# MCU.net
KiCad netlist of a schematic drawn in Altium Designer
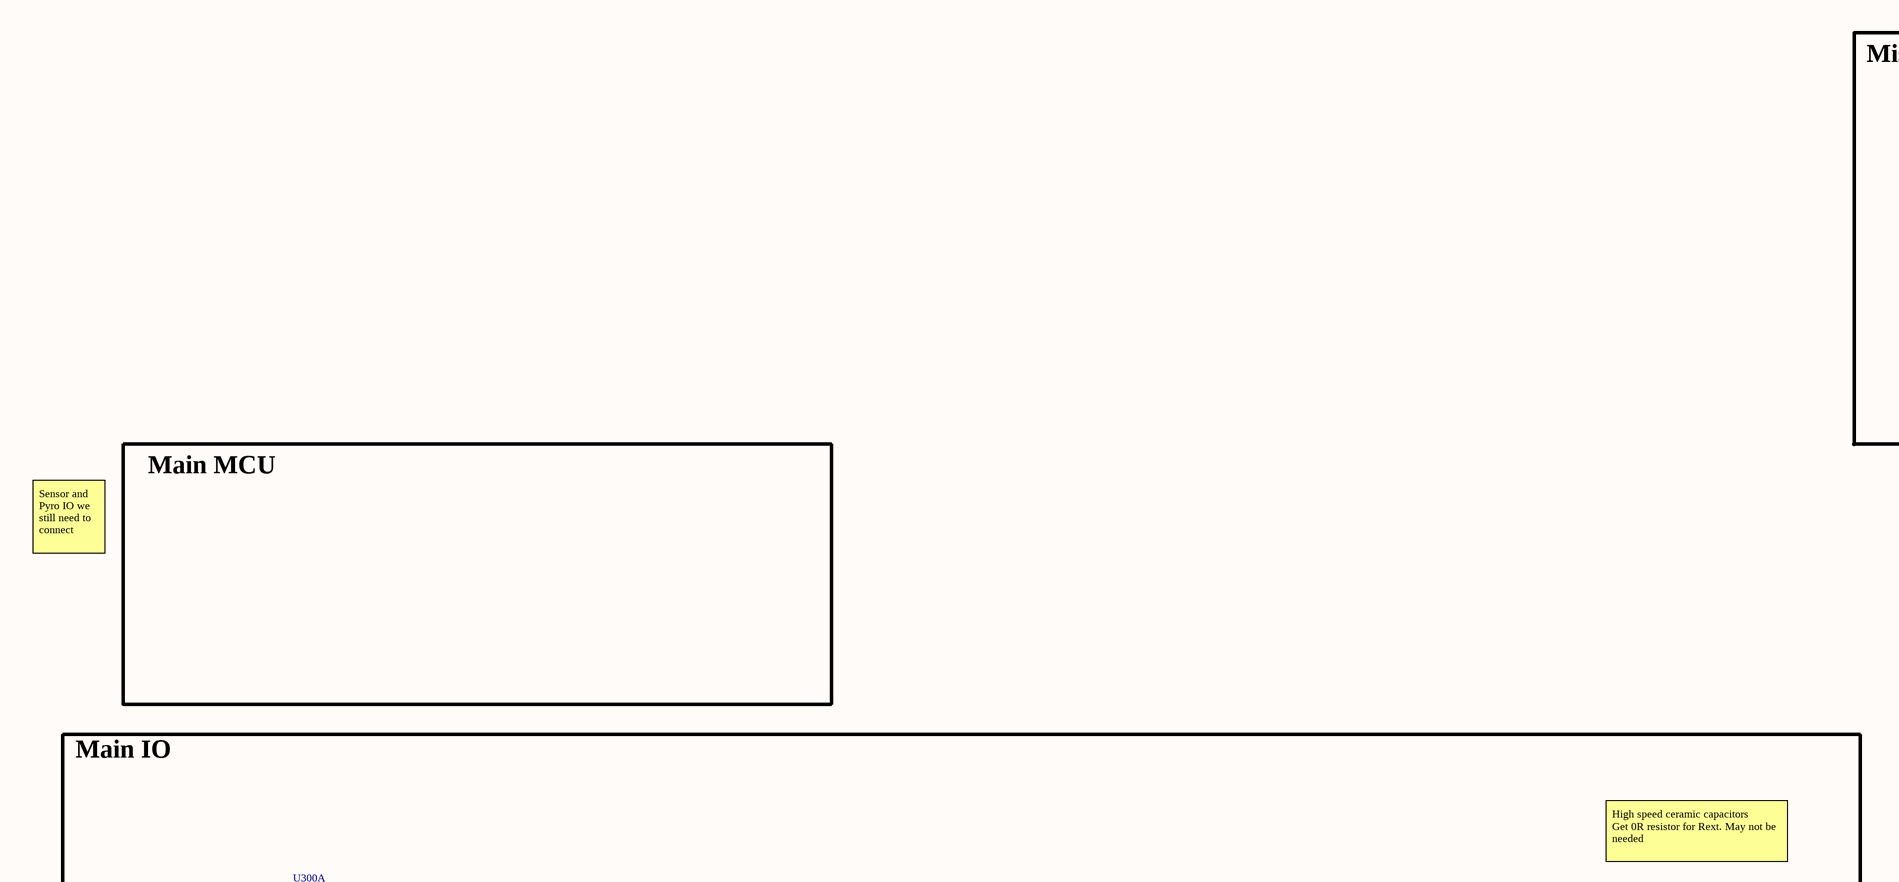
[diagram p0: MCU.SchDoc, top left]
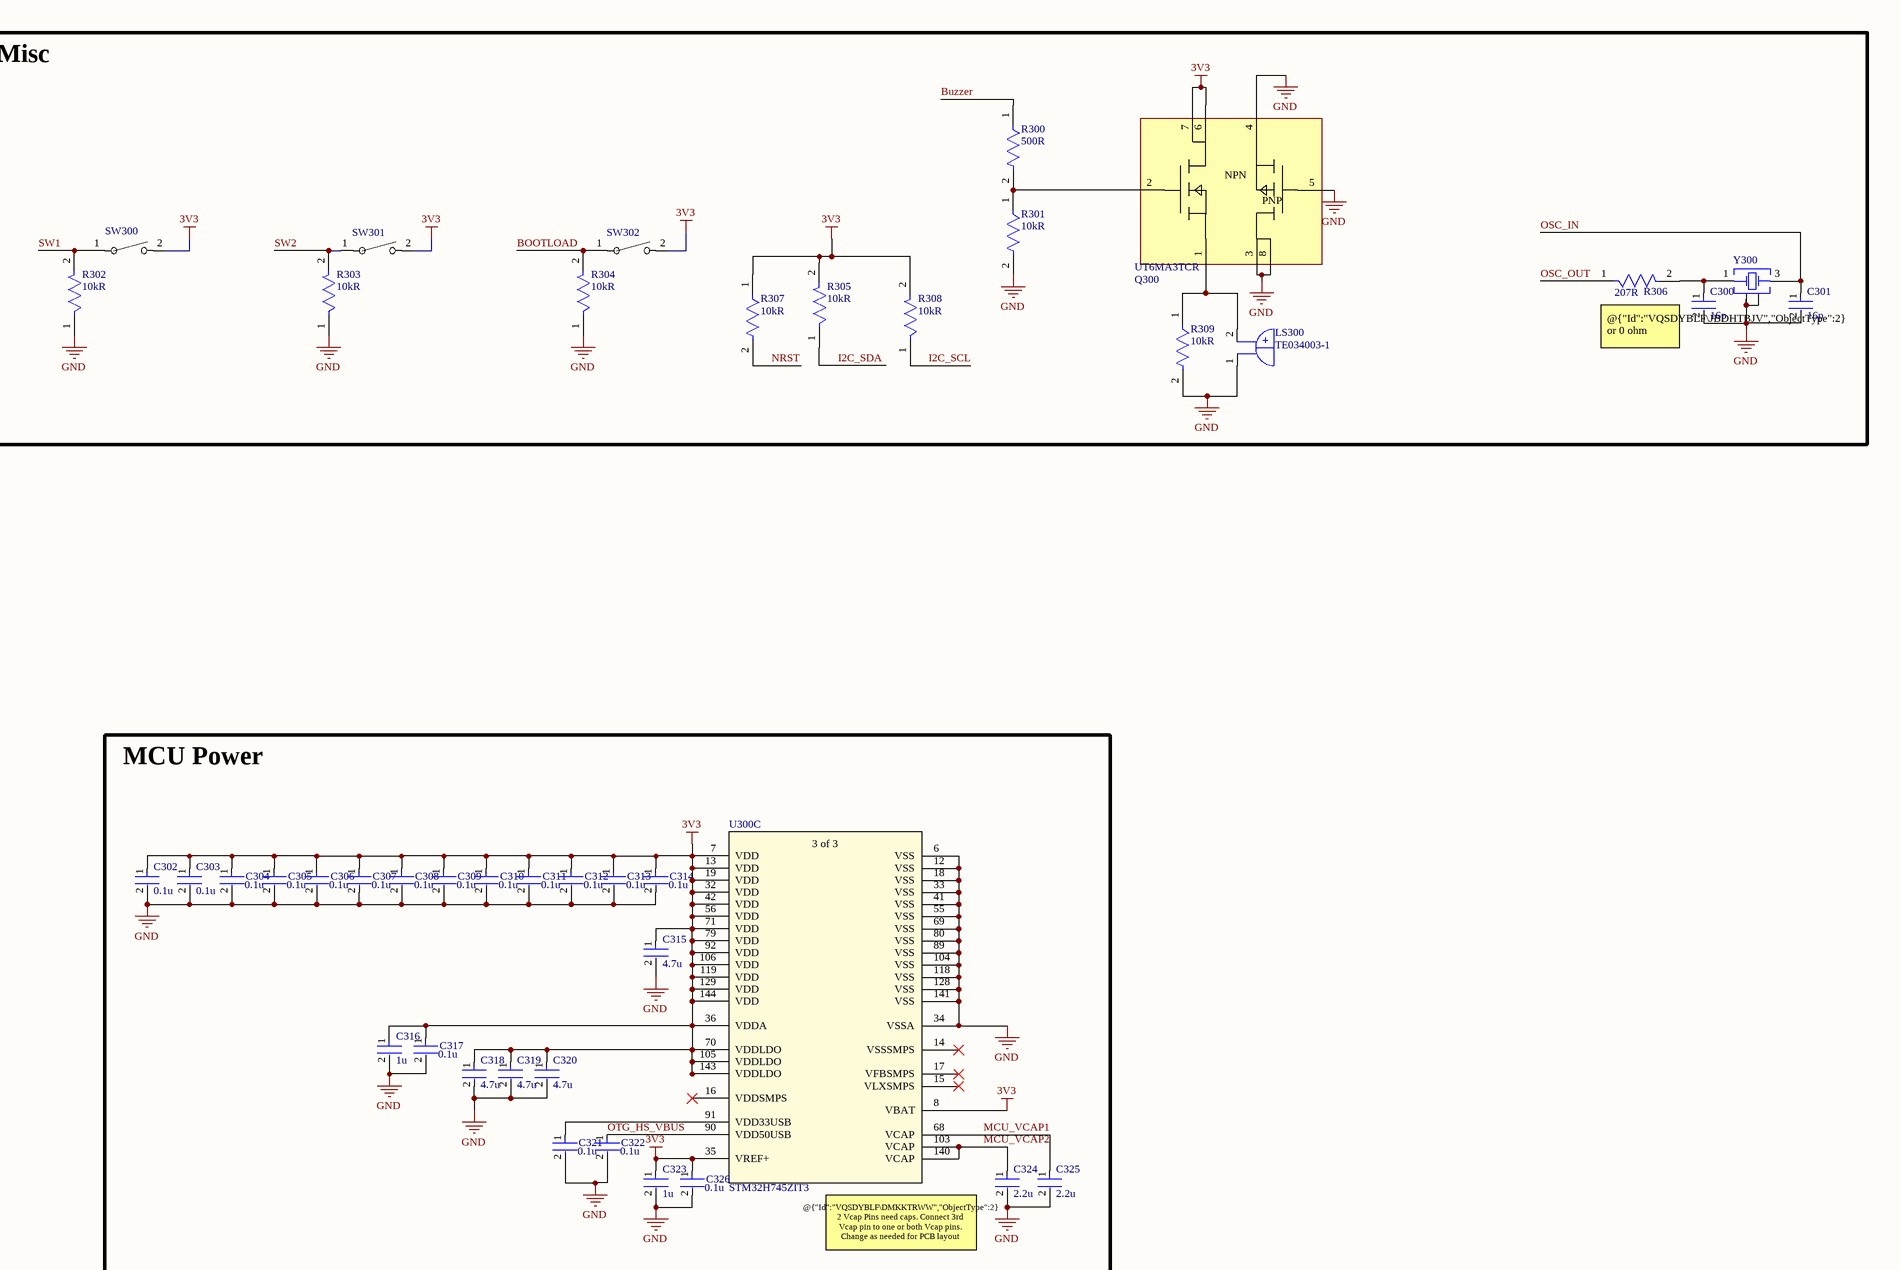
[diagram p1: MCU.SchDoc, top right]
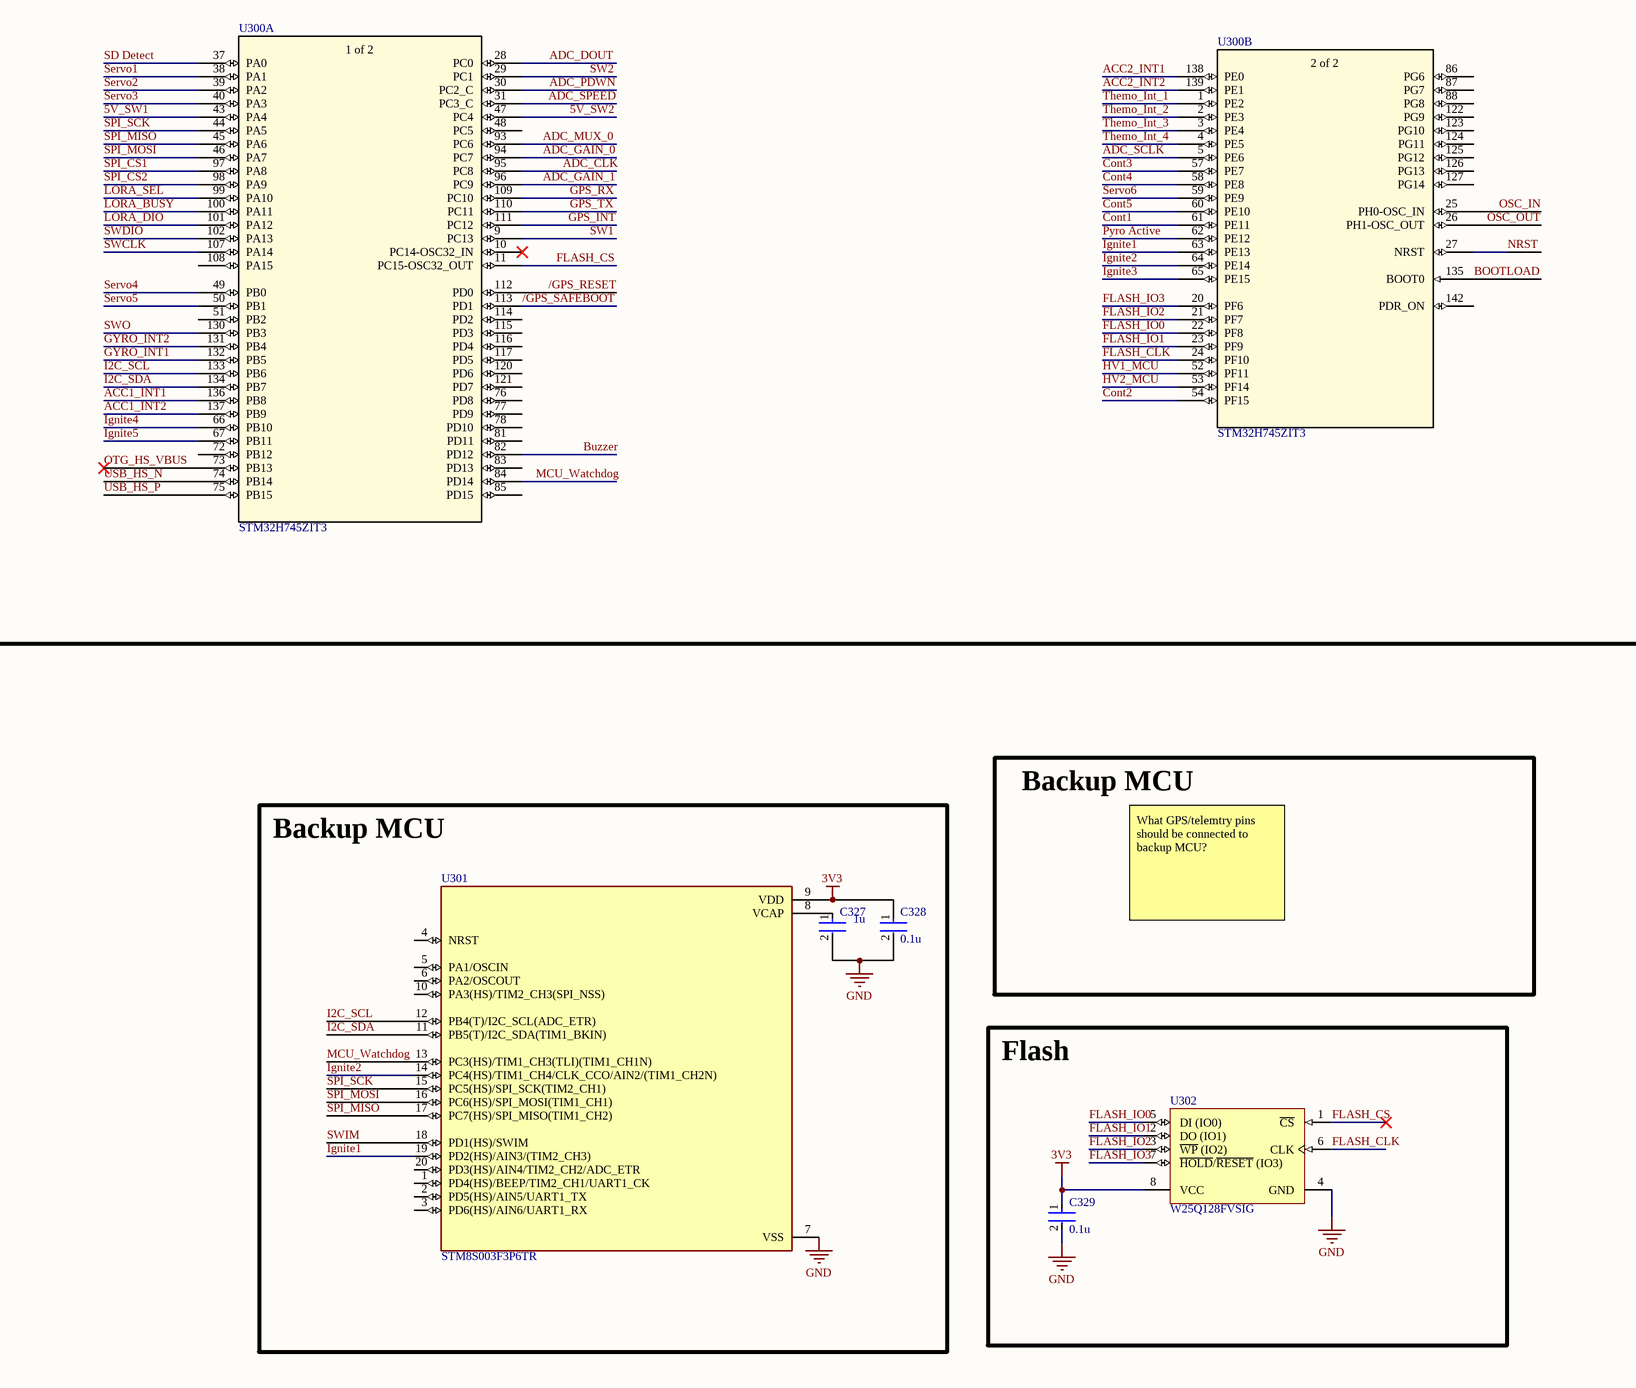
[diagram p2: MCU.SchDoc, bottom left]

(export (version "E")
  (design (tool "Eeschema 10.0.6"))
  (components
    (comp (ref "C300")
      (value "CL10C681JB8NFNC")
      (footprint "FP-CL10-IPC_A")
      (description "Cap Ceramic 680pF 50V C0G ±5% Pad SMD 0603 +125°C T/R")
      (fields (field (name "CAPACITANCE") "16p") (field (name "TOLERANCE") "5%"))
      (libsource (lib "Altium Content Vault") (part "b4654b650e69147ec39a6b967a45e02"))
    )
    (comp (ref "C301")
      (value "CL10C681JB8NFNC")
      (footprint "FP-CL10-IPC_A")
      (description "Cap Ceramic 680pF 50V C0G ±5% Pad SMD 0603 +125°C T/R")
      (fields (field (name "CAPACITANCE") "16p") (field (name "TOLERANCE") "5%"))
      (libsource (lib "Altium Content Vault") (part "b4654b650e69147ec39a6b967a45e02"))
    )
    (comp (ref "C302")
      (value "CL05B104KQ5NNNC")
      (footprint "FP-CL94-IPC_C")
      (description "Cap Ceramic 100nF 6.3V X7R ±10% SMD 0402 +125°C Paper T/R")
      (fields (field (name "TOLERANCE") "10%") (field (name "CAPACITANCE") "0.1u"))
      (libsource (lib "Altium Content Vault") (part "b4654b650e69147ec39a6b967a45e02"))
    )
    (comp (ref "C303")
      (value "CL05B104KQ5NNNC")
      (footprint "FP-CL94-IPC_C")
      (description "Cap Ceramic 100nF 6.3V X7R ±10% SMD 0402 +125°C Paper T/R")
      (fields (field (name "TOLERANCE") "10%") (field (name "CAPACITANCE") "0.1u"))
      (libsource (lib "Altium Content Vault") (part "b4654b650e69147ec39a6b967a45e02"))
    )
    (comp (ref "C304")
      (value "CL05B104KQ5NNNC")
      (footprint "FP-CL94-IPC_C")
      (description "Cap Ceramic 100nF 6.3V X7R ±10% SMD 0402 +125°C Paper T/R")
      (fields (field (name "TOLERANCE") "10%") (field (name "CAPACITANCE") "0.1u"))
      (libsource (lib "Altium Content Vault") (part "b4654b650e69147ec39a6b967a45e02"))
    )
    (comp (ref "C305")
      (value "CL05B104KQ5NNNC")
      (footprint "FP-CL94-IPC_C")
      (description "Cap Ceramic 100nF 6.3V X7R ±10% SMD 0402 +125°C Paper T/R")
      (fields (field (name "TOLERANCE") "10%") (field (name "CAPACITANCE") "0.1u"))
      (libsource (lib "Altium Content Vault") (part "b4654b650e69147ec39a6b967a45e02"))
    )
    (comp (ref "C306")
      (value "CL05B104KQ5NNNC")
      (footprint "FP-CL94-IPC_C")
      (description "Cap Ceramic 100nF 6.3V X7R ±10% SMD 0402 +125°C Paper T/R")
      (fields (field (name "TOLERANCE") "10%") (field (name "CAPACITANCE") "0.1u"))
      (libsource (lib "Altium Content Vault") (part "b4654b650e69147ec39a6b967a45e02"))
    )
    (comp (ref "C307")
      (value "CL05B104KQ5NNNC")
      (footprint "FP-CL94-IPC_C")
      (description "Cap Ceramic 100nF 6.3V X7R ±10% SMD 0402 +125°C Paper T/R")
      (fields (field (name "TOLERANCE") "10%") (field (name "CAPACITANCE") "0.1u"))
      (libsource (lib "Altium Content Vault") (part "b4654b650e69147ec39a6b967a45e02"))
    )
    (comp (ref "C308")
      (value "CL05B104KQ5NNNC")
      (footprint "FP-CL94-IPC_C")
      (description "Cap Ceramic 100nF 6.3V X7R ±10% SMD 0402 +125°C Paper T/R")
      (fields (field (name "TOLERANCE") "10%") (field (name "CAPACITANCE") "0.1u"))
      (libsource (lib "Altium Content Vault") (part "b4654b650e69147ec39a6b967a45e02"))
    )
    (comp (ref "C309")
      (value "CL05B104KQ5NNNC")
      (footprint "FP-CL94-IPC_C")
      (description "Cap Ceramic 100nF 6.3V X7R ±10% SMD 0402 +125°C Paper T/R")
      (fields (field (name "TOLERANCE") "10%") (field (name "CAPACITANCE") "0.1u"))
      (libsource (lib "Altium Content Vault") (part "b4654b650e69147ec39a6b967a45e02"))
    )
    (comp (ref "C310")
      (value "CL05B104KQ5NNNC")
      (footprint "FP-CL94-IPC_C")
      (description "Cap Ceramic 100nF 6.3V X7R ±10% SMD 0402 +125°C Paper T/R")
      (fields (field (name "TOLERANCE") "10%") (field (name "CAPACITANCE") "0.1u"))
      (libsource (lib "Altium Content Vault") (part "b4654b650e69147ec39a6b967a45e02"))
    )
    (comp (ref "C311")
      (value "CL05B104KQ5NNNC")
      (footprint "FP-CL94-IPC_C")
      (description "Cap Ceramic 100nF 6.3V X7R ±10% SMD 0402 +125°C Paper T/R")
      (fields (field (name "TOLERANCE") "10%") (field (name "CAPACITANCE") "0.1u"))
      (libsource (lib "Altium Content Vault") (part "b4654b650e69147ec39a6b967a45e02"))
    )
    (comp (ref "C312")
      (value "CL05B104KQ5NNNC")
      (footprint "FP-CL94-IPC_C")
      (description "Cap Ceramic 100nF 6.3V X7R ±10% SMD 0402 +125°C Paper T/R")
      (fields (field (name "TOLERANCE") "10%") (field (name "CAPACITANCE") "0.1u"))
      (libsource (lib "Altium Content Vault") (part "b4654b650e69147ec39a6b967a45e02"))
    )
    (comp (ref "C313")
      (value "CL05B104KQ5NNNC")
      (footprint "FP-CL94-IPC_C")
      (description "Cap Ceramic 100nF 6.3V X7R ±10% SMD 0402 +125°C Paper T/R")
      (fields (field (name "TOLERANCE") "10%") (field (name "CAPACITANCE") "0.1u"))
      (libsource (lib "Altium Content Vault") (part "b4654b650e69147ec39a6b967a45e02"))
    )
    (comp (ref "C314")
      (value "CL05B104KQ5NNNC")
      (footprint "FP-CL94-IPC_C")
      (description "Cap Ceramic 100nF 6.3V X7R ±10% SMD 0402 +125°C Paper T/R")
      (fields (field (name "TOLERANCE") "10%") (field (name "CAPACITANCE") "0.1u"))
      (libsource (lib "Altium Content Vault") (part "b4654b650e69147ec39a6b967a45e02"))
    )
    (comp (ref "C315")
      (value "CL10C681JB8NFNC")
      (footprint "FP-CL10-IPC_A")
      (description "Cap Ceramic 680pF 50V C0G ±5% Pad SMD 0603 +125°C T/R")
      (fields (field (name "CAPACITANCE") "4.7u") (field (name "TOLERANCE") "5%"))
      (libsource (lib "Altium Content Vault") (part "b4654b650e69147ec39a6b967a45e02"))
    )
    (comp (ref "C316")
      (value "CL10C681JB8NFNC")
      (footprint "FP-CL10-IPC_A")
      (description "Cap Ceramic 680pF 50V C0G ±5% Pad SMD 0603 +125°C T/R")
      (fields (field (name "CAPACITANCE") "1u") (field (name "TOLERANCE") "5%"))
      (libsource (lib "Altium Content Vault") (part "b4654b650e69147ec39a6b967a45e02"))
    )
    (comp (ref "C317")
      (value "CL05B104KQ5NNNC")
      (footprint "FP-CL94-IPC_C")
      (description "Cap Ceramic 100nF 6.3V X7R ±10% SMD 0402 +125°C Paper T/R")
      (fields (field (name "TOLERANCE") "10%") (field (name "CAPACITANCE") "0.1u"))
      (libsource (lib "Altium Content Vault") (part "b4654b650e69147ec39a6b967a45e02"))
    )
    (comp (ref "C318")
      (value "CL10C681JB8NFNC")
      (footprint "FP-CL10-IPC_A")
      (description "Cap Ceramic 680pF 50V C0G ±5% Pad SMD 0603 +125°C T/R")
      (fields (field (name "CAPACITANCE") "4.7u") (field (name "TOLERANCE") "5%"))
      (libsource (lib "Altium Content Vault") (part "b4654b650e69147ec39a6b967a45e02"))
    )
    (comp (ref "C319")
      (value "CL10C681JB8NFNC")
      (footprint "FP-CL10-IPC_A")
      (description "Cap Ceramic 680pF 50V C0G ±5% Pad SMD 0603 +125°C T/R")
      (fields (field (name "CAPACITANCE") "4.7u") (field (name "TOLERANCE") "5%"))
      (libsource (lib "Altium Content Vault") (part "b4654b650e69147ec39a6b967a45e02"))
    )
    (comp (ref "C320")
      (value "CL10C681JB8NFNC")
      (footprint "FP-CL10-IPC_A")
      (description "Cap Ceramic 680pF 50V C0G ±5% Pad SMD 0603 +125°C T/R")
      (fields (field (name "CAPACITANCE") "4.7u") (field (name "TOLERANCE") "5%"))
      (libsource (lib "Altium Content Vault") (part "b4654b650e69147ec39a6b967a45e02"))
    )
    (comp (ref "C321")
      (value "CL05B104KQ5NNNC")
      (footprint "FP-CL94-IPC_C")
      (description "Cap Ceramic 100nF 6.3V X7R ±10% SMD 0402 +125°C Paper T/R")
      (fields (field (name "TOLERANCE") "10%") (field (name "CAPACITANCE") "0.1u"))
      (libsource (lib "Altium Content Vault") (part "b4654b650e69147ec39a6b967a45e02"))
    )
    (comp (ref "C322")
      (value "CL05B104KQ5NNNC")
      (footprint "FP-CL94-IPC_C")
      (description "Cap Ceramic 100nF 6.3V X7R ±10% SMD 0402 +125°C Paper T/R")
      (fields (field (name "TOLERANCE") "10%") (field (name "CAPACITANCE") "0.1u"))
      (libsource (lib "Altium Content Vault") (part "b4654b650e69147ec39a6b967a45e02"))
    )
    (comp (ref "C323")
      (value "CL10C681JB8NFNC")
      (footprint "FP-CL10-IPC_A")
      (description "Cap Ceramic 680pF 50V C0G ±5% Pad SMD 0603 +125°C T/R")
      (fields (field (name "CAPACITANCE") "1u") (field (name "TOLERANCE") "5%"))
      (libsource (lib "Altium Content Vault") (part "b4654b650e69147ec39a6b967a45e02"))
    )
    (comp (ref "C324")
      (value "CL10C681JB8NFNC")
      (footprint "FP-CL10-IPC_A")
      (description "Cap Ceramic 680pF 50V C0G ±5% Pad SMD 0603 +125°C T/R")
      (fields (field (name "CAPACITANCE") "2.2u") (field (name "TOLERANCE") "5%"))
      (libsource (lib "Altium Content Vault") (part "b4654b650e69147ec39a6b967a45e02"))
    )
    (comp (ref "C325")
      (value "CL10C681JB8NFNC")
      (footprint "FP-CL10-IPC_A")
      (description "Cap Ceramic 680pF 50V C0G ±5% Pad SMD 0603 +125°C T/R")
      (fields (field (name "CAPACITANCE") "2.2u") (field (name "TOLERANCE") "5%"))
      (libsource (lib "Altium Content Vault") (part "b4654b650e69147ec39a6b967a45e02"))
    )
    (comp (ref "C326")
      (value "CL05B104KQ5NNNC")
      (footprint "FP-CL94-IPC_C")
      (description "Cap Ceramic 100nF 6.3V X7R ±10% SMD 0402 +125°C Paper T/R")
      (fields (field (name "TOLERANCE") "10%") (field (name "CAPACITANCE") "0.1u"))
      (libsource (lib "Altium Content Vault") (part "b4654b650e69147ec39a6b967a45e02"))
    )
    (comp (ref "C327")
      (value "CL10C681JB8NFNC")
      (footprint "FP-CL10-IPC_A")
      (description "Cap Ceramic 680pF 50V C0G ±5% Pad SMD 0603 +125°C T/R")
      (fields (field (name "CAPACITANCE") "1u") (field (name "TOLERANCE") "5%"))
      (libsource (lib "Altium Content Vault") (part "b4654b650e69147ec39a6b967a45e02"))
    )
    (comp (ref "C328")
      (value "CL10C681JB8NFNC")
      (footprint "FP-CL10-IPC_A")
      (description "Cap Ceramic 680pF 50V C0G ±5% Pad SMD 0603 +125°C T/R")
      (fields (field (name "CAPACITANCE") "0.1u") (field (name "TOLERANCE") "5%"))
      (libsource (lib "Altium Content Vault") (part "b4654b650e69147ec39a6b967a45e02"))
    )
    (comp (ref "C329")
      (value "CL10C681JB8NFNC")
      (footprint "FP-CL10-IPC_A")
      (description "Cap Ceramic 680pF 50V C0G ±5% Pad SMD 0603 +125°C T/R")
      (fields (field (name "CAPACITANCE") "0.1u") (field (name "TOLERANCE") "5%"))
      (libsource (lib "Altium Content Vault") (part "b4654b650e69147ec39a6b967a45e02"))
    )
    (comp (ref "LS300")
      (value "TE034003-1")
      (footprint "XDCR_TE034003-1")
      (fields (field (name "MF") "DB Unlimited"))
      (libsource (lib "Erich Robb") (part "TE034003-1"))
    )
    (comp (ref "Q300")
      (value "UT6MA3TCR")
      (footprint "TRANS_UT6J3_ROM")
      (description "No Description Available")
      (libsource (lib "Erich Robb") (part "UT6MA3TCR"))
    )
    (comp (ref "R300")
      (value "500R")
      (footprint "FP-CPF0603-MFG")
      (description "RES SMD 2.15KΩ 0.1% 1/16W 0603")
      (fields
        (field (name "MANUFACTURER") "TE Connectivity")
        (field (name "OCTOPART") "https://octopart.com/cpf0603b2k15e1-te+connectivity-22739551")
      )
      (libsource (lib "Altium Content Vault") (part "1029c3af85768c4190bb7ad29bc67b5"))
    )
    (comp (ref "R301")
      (value "10kR")
      (footprint "FP-CPF0603-MFG")
      (description "RES SMD 2.15KΩ 0.1% 1/16W 0603")
      (fields
        (field (name "MANUFACTURER") "TE Connectivity")
        (field (name "OCTOPART") "https://octopart.com/cpf0603b2k15e1-te+connectivity-22739551")
      )
      (libsource (lib "Altium Content Vault") (part "1029c3af85768c4190bb7ad29bc67b5"))
    )
    (comp (ref "R302")
      (value "10kR")
      (footprint "FP-CPF0603-MFG")
      (description "RES SMD 2.15KΩ 0.1% 1/16W 0603")
      (fields
        (field (name "MANUFACTURER") "TE Connectivity")
        (field (name "OCTOPART") "https://octopart.com/cpf0603b2k15e1-te+connectivity-22739551")
      )
      (libsource (lib "Altium Content Vault") (part "1029c3af85768c4190bb7ad29bc67b5"))
    )
    (comp (ref "R303")
      (value "10kR")
      (footprint "FP-CPF0603-MFG")
      (description "RES SMD 2.15KΩ 0.1% 1/16W 0603")
      (fields
        (field (name "MANUFACTURER") "TE Connectivity")
        (field (name "OCTOPART") "https://octopart.com/cpf0603b2k15e1-te+connectivity-22739551")
      )
      (libsource (lib "Altium Content Vault") (part "1029c3af85768c4190bb7ad29bc67b5"))
    )
    (comp (ref "R304")
      (value "10kR")
      (footprint "FP-CPF0603-MFG")
      (description "RES SMD 2.15KΩ 0.1% 1/16W 0603")
      (fields
        (field (name "MANUFACTURER") "TE Connectivity")
        (field (name "OCTOPART") "https://octopart.com/cpf0603b2k15e1-te+connectivity-22739551")
      )
      (libsource (lib "Altium Content Vault") (part "1029c3af85768c4190bb7ad29bc67b5"))
    )
    (comp (ref "R305")
      (value "10kR")
      (footprint "FP-CPF0603-MFG")
      (description "RES SMD 2.15KΩ 0.1% 1/16W 0603")
      (fields
        (field (name "MANUFACTURER") "TE Connectivity")
        (field (name "OCTOPART") "https://octopart.com/cpf0603b2k15e1-te+connectivity-22739551")
      )
      (libsource (lib "Altium Content Vault") (part "1029c3af85768c4190bb7ad29bc67b5"))
    )
    (comp (ref "R306")
      (value "207R")
      (footprint "FP-CPF0603-MFG")
      (description "RES SMD 2.15KΩ 0.1% 1/16W 0603")
      (fields
        (field (name "MANUFACTURER") "TE Connectivity")
        (field (name "OCTOPART") "https://octopart.com/cpf0603b2k15e1-te+connectivity-22739551")
      )
      (libsource (lib "Altium Content Vault") (part "1029c3af85768c4190bb7ad29bc67b5"))
    )
    (comp (ref "R307")
      (value "10kR")
      (footprint "FP-CPF0603-MFG")
      (description "RES SMD 2.15KΩ 0.1% 1/16W 0603")
      (fields
        (field (name "MANUFACTURER") "TE Connectivity")
        (field (name "OCTOPART") "https://octopart.com/cpf0603b2k15e1-te+connectivity-22739551")
      )
      (libsource (lib "Altium Content Vault") (part "1029c3af85768c4190bb7ad29bc67b5"))
    )
    (comp (ref "R308")
      (value "10kR")
      (footprint "FP-CPF0603-MFG")
      (description "RES SMD 2.15KΩ 0.1% 1/16W 0603")
      (fields
        (field (name "MANUFACTURER") "TE Connectivity")
        (field (name "OCTOPART") "https://octopart.com/cpf0603b2k15e1-te+connectivity-22739551")
      )
      (libsource (lib "Altium Content Vault") (part "1029c3af85768c4190bb7ad29bc67b5"))
    )
    (comp (ref "R309")
      (value "10kR")
      (footprint "FP-CPF0603-MFG")
      (description "RES SMD 2.15KΩ 0.1% 1/16W 0603")
      (fields
        (field (name "MANUFACTURER") "TE Connectivity")
        (field (name "OCTOPART") "https://octopart.com/cpf0603b2k15e1-te+connectivity-22739551")
      )
      (libsource (lib "Altium Content Vault") (part "1029c3af85768c4190bb7ad29bc67b5"))
    )
    (comp (ref "SW300")
      (value "PTS636SL43SMTRLFS")
      (footprint "SW_PTS636S-J_CNK")
      (description "No Description Available")
      (libsource (lib "Erich Robb") (part "PTS636SL43SMTRLFS"))
    )
    (comp (ref "SW301")
      (value "PTS636SL43SMTRLFS")
      (footprint "SW_PTS636S-J_CNK")
      (description "No Description Available")
      (libsource (lib "Erich Robb") (part "PTS636SL43SMTRLFS"))
    )
    (comp (ref "SW302")
      (value "PTS636SL43SMTRLFS")
      (footprint "SW_PTS636S-J_CNK")
      (description "No Description Available")
      (libsource (lib "Erich Robb") (part "PTS636SL43SMTRLFS"))
    )
    (comp (ref "U300")
      (value "STM32H745ZIT3")
      (footprint "LQFP-144")
      (description "32-bit Dual Core, 144 Pin, 97 IO, 1M RAM, 2M Flash")
      (libsource (lib "Erich Robb") (part "STM32H745ZIT3"))
    )
    (comp (ref "U301")
      (value "STM8S003F3P6TR")
      (footprint "SOP65P640X120-20N")
      (description "STM8 STM8S Microcontroller IC 8-Bit 16MHz 8KB (8K x 8) FLASH 20-TSSOP")
      (fields (field (name "MF") "STMicroelectronics"))
      (libsource (lib "Erich Robb") (part "STM8S003F3P6TR"))
    )
    (comp (ref "U302")
      (value "W25Q128FVSIG")
      (footprint "WINB-SOIC-8_M")
      (fields (field (name "MANUFACTURER") "Winbond"))
      (libsource (lib "Altium Content Vault") (part "WINB-W25Q128FVSIG-SOIC-8"))
    )
    (comp (ref "Y300")
      (value "830108213509")
      (footprint "WE-XTAL_IQXC-42")
      (description "WE-XTAL Quartz Crystal, SMT, IQXC-42, 48MHz, +/-10ppm")
      (fields (field (name "MANUFACTURER") "Wurth Elektronik"))
      (libsource (lib "Erich Robb") (part "830108213509"))
    )
  )
  (nets
    (net (code "1") (name "/5V_SW1") (class "Default")
      (node (ref "U300") (pin "43") (pinfunction "PA4_43") (pintype "bidirectional"))
    )
    (net (code "2") (name "/5V_SW2") (class "Default")
      (node (ref "U300") (pin "47") (pinfunction "PC4_47") (pintype "bidirectional"))
    )
    (net (code "4") (name "/ACC1_INT1") (class "Default")
      (node (ref "U300") (pin "136") (pinfunction "PB8_136") (pintype "bidirectional"))
    )
    (net (code "5") (name "/ACC1_INT2") (class "Default")
      (node (ref "U300") (pin "137") (pinfunction "PB9_137") (pintype "bidirectional"))
    )
    (net (code "6") (name "/ACC2_INT1") (class "Default")
      (node (ref "U300") (pin "138") (pinfunction "PE0_138") (pintype "bidirectional"))
    )
    (net (code "7") (name "/ACC2_INT2") (class "Default")
      (node (ref "U300") (pin "139") (pinfunction "PE1_139") (pintype "bidirectional"))
    )
    (net (code "8") (name "/ADC_CLK") (class "Default")
      (node (ref "U300") (pin "95") (pinfunction "PC8_95") (pintype "bidirectional"))
    )
    (net (code "9") (name "/ADC_DOUT") (class "Default")
      (node (ref "U300") (pin "28") (pinfunction "PC0_28") (pintype "bidirectional"))
    )
    (net (code "10") (name "/ADC_GAIN_0") (class "Default")
      (node (ref "U300") (pin "94") (pinfunction "PC7_94") (pintype "bidirectional"))
    )
    (net (code "11") (name "/ADC_GAIN_1") (class "Default")
      (node (ref "U300") (pin "96") (pinfunction "PC9_96") (pintype "bidirectional"))
    )
    (net (code "12") (name "/ADC_MUX_0") (class "Default")
      (node (ref "U300") (pin "93") (pinfunction "PC6_93") (pintype "bidirectional"))
    )
    (net (code "13") (name "/ADC_PDWN") (class "Default")
      (node (ref "U300") (pin "30") (pinfunction "PC2_C_30") (pintype "bidirectional"))
    )
    (net (code "14") (name "/ADC_SCLK") (class "Default")
      (node (ref "U300") (pin "5") (pinfunction "PE6_5") (pintype "bidirectional"))
    )
    (net (code "15") (name "/ADC_SPEED") (class "Default")
      (node (ref "U300") (pin "31") (pinfunction "PC3_C_31") (pintype "bidirectional"))
    )
    (net (code "16") (name "/BOOTLOAD") (class "Default")
      (node (ref "R304") (pin "2") (pinfunction "2_2") (pintype "passive"))
      (node (ref "SW302") (pin "1") (pinfunction "1_1") (pintype "passive"))
      (node (ref "U300") (pin "135") (pinfunction "BOOT0_135") (pintype "input"))
    )
    (net (code "17") (name "/Buzzer") (class "Default")
      (node (ref "R300") (pin "1") (pinfunction "1_1") (pintype "passive"))
      (node (ref "U300") (pin "82") (pinfunction "PD12_82") (pintype "bidirectional"))
    )
    (net (code "18") (name "/Cont1") (class "Default")
      (node (ref "U300") (pin "61") (pinfunction "PE11_61") (pintype "bidirectional"))
    )
    (net (code "19") (name "/Cont2") (class "Default")
      (node (ref "U300") (pin "54") (pinfunction "PF15_54") (pintype "bidirectional"))
    )
    (net (code "20") (name "/Cont3") (class "Default")
      (node (ref "U300") (pin "57") (pinfunction "PE7_57") (pintype "bidirectional"))
    )
    (net (code "21") (name "/Cont4") (class "Default")
      (node (ref "U300") (pin "58") (pinfunction "PE8_58") (pintype "bidirectional"))
    )
    (net (code "22") (name "/Cont5") (class "Default")
      (node (ref "U300") (pin "60") (pinfunction "PE10_60") (pintype "bidirectional"))
    )
    (net (code "23") (name "/FLASH_CLK") (class "Default")
      (node (ref "U300") (pin "24") (pinfunction "PF10_24") (pintype "bidirectional"))
      (node (ref "U302") (pin "6") (pinfunction "CLK_6") (pintype "input"))
    )
    (net (code "24") (name "/FLASH_CS") (class "Default")
      (node (ref "U300") (pin "11") (pinfunction "PC15-OSC32_OUT_11") (pintype "bidirectional"))
      (node (ref "U302") (pin "1") (pinfunction "~{CS}_1") (pintype "input"))
    )
    (net (code "25") (name "/FLASH_IO0") (class "Default")
      (node (ref "U300") (pin "22") (pinfunction "PF8_22") (pintype "bidirectional"))
      (node (ref "U302") (pin "5") (pinfunction "DI_(IO0)_5") (pintype "bidirectional"))
    )
    (net (code "26") (name "/FLASH_IO1") (class "Default")
      (node (ref "U300") (pin "23") (pinfunction "PF9_23") (pintype "bidirectional"))
      (node (ref "U302") (pin "2") (pinfunction "DO_(IO1)_2") (pintype "bidirectional"))
    )
    (net (code "27") (name "/FLASH_IO2") (class "Default")
      (node (ref "U300") (pin "21") (pinfunction "PF7_21") (pintype "bidirectional"))
      (node (ref "U302") (pin "3") (pinfunction "~{WP}_(IO2)_3") (pintype "bidirectional"))
    )
    (net (code "28") (name "/FLASH_IO3") (class "Default")
      (node (ref "U300") (pin "20") (pinfunction "PF6_20") (pintype "bidirectional"))
      (node (ref "U302") (pin "7") (pinfunction "~{HOLD}/~{RESET}_(IO3)_7") (pintype "bidirectional"))
    )
    (net (code "29") (name "/GPS_INT") (class "Default")
      (node (ref "U300") (pin "111") (pinfunction "PC12_111") (pintype "bidirectional"))
    )
    (net (code "30") (name "/GPS_RX") (class "Default")
      (node (ref "U300") (pin "109") (pinfunction "PC10_109") (pintype "bidirectional"))
    )
    (net (code "31") (name "/GPS_TX") (class "Default")
      (node (ref "U300") (pin "110") (pinfunction "PC11_110") (pintype "bidirectional"))
    )
    (net (code "32") (name "/GYRO_INT1") (class "Default")
      (node (ref "U300") (pin "132") (pinfunction "PB5_132") (pintype "bidirectional"))
    )
    (net (code "33") (name "/GYRO_INT2") (class "Default")
      (node (ref "U300") (pin "131") (pinfunction "PB4_131") (pintype "bidirectional"))
    )
    (net (code "34") (name "/HV1_MCU") (class "Default")
      (node (ref "U300") (pin "52") (pinfunction "PF11_52") (pintype "bidirectional"))
    )
    (net (code "35") (name "/HV2_MCU") (class "Default")
      (node (ref "U300") (pin "53") (pinfunction "PF14_53") (pintype "bidirectional"))
    )
    (net (code "36") (name "/I2C_SCL") (class "Default")
      (node (ref "R308") (pin "1") (pinfunction "1_1") (pintype "passive"))
      (node (ref "U300") (pin "133") (pinfunction "PB6_133") (pintype "bidirectional"))
      (node (ref "U301") (pin "12") (pinfunction "PB4(T)/I2C_SCL(ADC_ETR)_12") (pintype "bidirectional"))
    )
    (net (code "37") (name "/I2C_SDA") (class "Default")
      (node (ref "R305") (pin "1") (pinfunction "1_1") (pintype "passive"))
      (node (ref "U300") (pin "134") (pinfunction "PB7_134") (pintype "bidirectional"))
      (node (ref "U301") (pin "11") (pinfunction "PB5(T)/I2C_SDA(TIM1_BKIN)_11") (pintype "bidirectional"))
    )
    (net (code "38") (name "/Ignite1") (class "Default")
      (node (ref "U300") (pin "63") (pinfunction "PE13_63") (pintype "bidirectional"))
      (node (ref "U301") (pin "19") (pinfunction "PD2(HS)/AIN3/(TIM2_CH3)_19") (pintype "bidirectional"))
    )
    (net (code "39") (name "/Ignite2") (class "Default")
      (node (ref "U300") (pin "64") (pinfunction "PE14_64") (pintype "bidirectional"))
      (node (ref "U301") (pin "14") (pinfunction "PC4(HS)/TIM1_CH4/CLK_CCO/AIN2/(TIM1_CH2N)_14") (pintype "bidirectional"))
    )
    (net (code "40") (name "/Ignite3") (class "Default")
      (node (ref "U300") (pin "65") (pinfunction "PE15_65") (pintype "bidirectional"))
    )
    (net (code "41") (name "/Ignite4") (class "Default")
      (node (ref "U300") (pin "66") (pinfunction "PB10_66") (pintype "bidirectional"))
    )
    (net (code "42") (name "/Ignite5") (class "Default")
      (node (ref "U300") (pin "67") (pinfunction "PB11_67") (pintype "bidirectional"))
    )
    (net (code "43") (name "/LORA_BUSY") (class "Default")
      (node (ref "U300") (pin "100") (pinfunction "PA11_100") (pintype "bidirectional"))
    )
    (net (code "44") (name "/LORA_DIO") (class "Default")
      (node (ref "U300") (pin "101") (pinfunction "PA12_101") (pintype "bidirectional"))
    )
    (net (code "45") (name "/LORA_SEL") (class "Default")
      (node (ref "U300") (pin "99") (pinfunction "PA10_99") (pintype "bidirectional"))
    )
    (net (code "46") (name "/MCU_VCAP1") (class "Default")
      (node (ref "C325") (pin "1") (pinfunction "1_1") (pintype "passive"))
      (node (ref "U300") (pin "68") (pinfunction "VCAP_68") (pintype "power_in"))
    )
    (net (code "47") (name "/MCU_VCAP2") (class "Default")
      (node (ref "C324") (pin "1") (pinfunction "1_1") (pintype "passive"))
      (node (ref "U300") (pin "103") (pinfunction "VCAP_103") (pintype "power_in"))
      (node (ref "U300") (pin "140") (pinfunction "VCAP_140") (pintype "power_in"))
    )
    (net (code "48") (name "/MCU_Watchdog") (class "Default")
      (node (ref "U300") (pin "84") (pinfunction "PD14_84") (pintype "bidirectional"))
      (node (ref "U301") (pin "13") (pinfunction "PC3(HS)/TIM1_CH3(TLI)(TIM1_CH1N)_13") (pintype "bidirectional"))
    )
    (net (code "49") (name "/NRST") (class "Default")
      (node (ref "R307") (pin "2") (pinfunction "2_2") (pintype "passive"))
      (node (ref "U300") (pin "27") (pinfunction "NRST_27") (pintype "bidirectional"))
    )
    (net (code "50") (name "/OSC_IN") (class "Default")
      (node (ref "C301") (pin "1") (pinfunction "1_1") (pintype "passive"))
      (node (ref "U300") (pin "25") (pinfunction "PH0-OSC_IN_25") (pintype "bidirectional"))
      (node (ref "Y300") (pin "3") (pinfunction "Crystal_3") (pintype "passive"))
    )
    (net (code "51") (name "/OSC_OUT") (class "Default")
      (node (ref "R306") (pin "1") (pinfunction "1_1") (pintype "passive"))
      (node (ref "U300") (pin "26") (pinfunction "PH1-OSC_OUT_26") (pintype "bidirectional"))
    )
    (net (code "52") (name "/OTG_HS_VBUS") (class "Default")
      (node (ref "C322") (pin "1") (pinfunction "1_1") (pintype "passive"))
      (node (ref "U300") (pin "73") (pinfunction "PB13_73") (pintype "bidirectional"))
      (node (ref "U300") (pin "90") (pinfunction "VDD50USB_90") (pintype "power_in"))
    )
    (net (code "53") (name "/Pyro Active") (class "Default")
      (node (ref "U300") (pin "62") (pinfunction "PE12_62") (pintype "bidirectional"))
    )
    (net (code "54") (name "/SD Detect") (class "Default")
      (node (ref "U300") (pin "37") (pinfunction "PA0_37") (pintype "bidirectional"))
    )
    (net (code "55") (name "/SPI_CS1") (class "Default")
      (node (ref "U300") (pin "97") (pinfunction "PA8_97") (pintype "bidirectional"))
    )
    (net (code "56") (name "/SPI_CS2") (class "Default")
      (node (ref "U300") (pin "98") (pinfunction "PA9_98") (pintype "bidirectional"))
    )
    (net (code "57") (name "/SPI_MISO") (class "Default")
      (node (ref "U300") (pin "45") (pinfunction "PA6_45") (pintype "bidirectional"))
      (node (ref "U301") (pin "17") (pinfunction "PC7(HS)/SPI_MISO(TIM1_CH2)_17") (pintype "bidirectional"))
    )
    (net (code "58") (name "/SPI_MOSI") (class "Default")
      (node (ref "U300") (pin "46") (pinfunction "PA7_46") (pintype "bidirectional"))
      (node (ref "U301") (pin "16") (pinfunction "PC6(HS)/SPI_MOSI(TIM1_CH1)_16") (pintype "bidirectional"))
    )
    (net (code "59") (name "/SPI_SCK") (class "Default")
      (node (ref "U300") (pin "44") (pinfunction "PA5_44") (pintype "bidirectional"))
      (node (ref "U301") (pin "15") (pinfunction "PC5(HS)/SPI_SCK(TIM2_CH1)_15") (pintype "bidirectional"))
    )
    (net (code "60") (name "/SW1") (class "Default")
      (node (ref "R302") (pin "2") (pinfunction "2_2") (pintype "passive"))
      (node (ref "SW300") (pin "1") (pinfunction "1_1") (pintype "passive"))
      (node (ref "U300") (pin "9") (pinfunction "PC13_9") (pintype "bidirectional"))
    )
    (net (code "61") (name "/SW2") (class "Default")
      (node (ref "R303") (pin "2") (pinfunction "2_2") (pintype "passive"))
      (node (ref "SW301") (pin "1") (pinfunction "1_1") (pintype "passive"))
      (node (ref "U300") (pin "29") (pinfunction "PC1_29") (pintype "bidirectional"))
    )
    (net (code "62") (name "/SWCLK") (class "Default")
      (node (ref "U300") (pin "107") (pinfunction "PA14_107") (pintype "bidirectional"))
    )
    (net (code "63") (name "/SWDIO") (class "Default")
      (node (ref "U300") (pin "102") (pinfunction "PA13_102") (pintype "bidirectional"))
    )
    (net (code "64") (name "/SWIM") (class "Default")
      (node (ref "U301") (pin "18") (pinfunction "PD1(HS)/SWIM_18") (pintype "bidirectional"))
    )
    (net (code "65") (name "/SWO") (class "Default")
      (node (ref "U300") (pin "130") (pinfunction "PB3_130") (pintype "bidirectional"))
    )
    (net (code "66") (name "/Servo1") (class "Default")
      (node (ref "U300") (pin "38") (pinfunction "PA1_38") (pintype "bidirectional"))
    )
    (net (code "67") (name "/Servo2") (class "Default")
      (node (ref "U300") (pin "39") (pinfunction "PA2_39") (pintype "bidirectional"))
    )
    (net (code "68") (name "/Servo3") (class "Default")
      (node (ref "U300") (pin "40") (pinfunction "PA3_40") (pintype "bidirectional"))
    )
    (net (code "69") (name "/Servo4") (class "Default")
      (node (ref "U300") (pin "49") (pinfunction "PB0_49") (pintype "bidirectional"))
    )
    (net (code "70") (name "/Servo5") (class "Default")
      (node (ref "U300") (pin "50") (pinfunction "PB1_50") (pintype "bidirectional"))
    )
    (net (code "71") (name "/Servo6") (class "Default")
      (node (ref "U300") (pin "59") (pinfunction "PE9_59") (pintype "bidirectional"))
    )
    (net (code "72") (name "/Themo_Int_1") (class "Default")
      (node (ref "U300") (pin "1") (pinfunction "PE2_1") (pintype "bidirectional"))
    )
    (net (code "73") (name "/Themo_Int_2") (class "Default")
      (node (ref "U300") (pin "2") (pinfunction "PE3_2") (pintype "bidirectional"))
    )
    (net (code "74") (name "/Themo_Int_3") (class "Default")
      (node (ref "U300") (pin "3") (pinfunction "PE4_3") (pintype "bidirectional"))
    )
    (net (code "75") (name "/Themo_Int_4") (class "Default")
      (node (ref "U300") (pin "4") (pinfunction "PE5_4") (pintype "bidirectional"))
    )
    (net (code "76") (name "/USB_HS_N") (class "Default")
      (node (ref "U300") (pin "74") (pinfunction "PB14_74") (pintype "bidirectional"))
    )
    (net (code "77") (name "/USB_HS_P") (class "Default")
      (node (ref "U300") (pin "75") (pinfunction "PB15_75") (pintype "bidirectional"))
    )
    (net (code "78") (name "/{slash}GPS_RESET") (class "Default")
      (node (ref "U300") (pin "112") (pinfunction "PD0_112") (pintype "bidirectional"))
    )
    (net (code "79") (name "/{slash}GPS_SAFEBOOT") (class "Default")
      (node (ref "U300") (pin "113") (pinfunction "PD1_113") (pintype "bidirectional"))
    )
    (net (code "80") (name "3V3") (class "Default")
      (node (ref "C302") (pin "1") (pinfunction "1_1") (pintype "passive"))
      (node (ref "C303") (pin "1") (pinfunction "1_1") (pintype "passive"))
      (node (ref "C304") (pin "1") (pinfunction "1_1") (pintype "passive"))
      (node (ref "C305") (pin "1") (pinfunction "1_1") (pintype "passive"))
      (node (ref "C306") (pin "1") (pinfunction "1_1") (pintype "passive"))
      (node (ref "C307") (pin "1") (pinfunction "1_1") (pintype "passive"))
      (node (ref "C308") (pin "1") (pinfunction "1_1") (pintype "passive"))
      (node (ref "C309") (pin "1") (pinfunction "1_1") (pintype "passive"))
      (node (ref "C310") (pin "1") (pinfunction "1_1") (pintype "passive"))
      (node (ref "C311") (pin "1") (pinfunction "1_1") (pintype "passive"))
      (node (ref "C312") (pin "1") (pinfunction "1_1") (pintype "passive"))
      (node (ref "C313") (pin "1") (pinfunction "1_1") (pintype "passive"))
      (node (ref "C314") (pin "1") (pinfunction "1_1") (pintype "passive"))
      (node (ref "C315") (pin "1") (pinfunction "1_1") (pintype "passive"))
      (node (ref "C316") (pin "1") (pinfunction "1_1") (pintype "passive"))
      (node (ref "C317") (pin "1") (pinfunction "1_1") (pintype "passive"))
      (node (ref "C318") (pin "1") (pinfunction "1_1") (pintype "passive"))
      (node (ref "C319") (pin "1") (pinfunction "1_1") (pintype "passive"))
      (node (ref "C320") (pin "1") (pinfunction "1_1") (pintype "passive"))
      (node (ref "C323") (pin "1") (pinfunction "1_1") (pintype "passive"))
      (node (ref "C326") (pin "1") (pinfunction "1_1") (pintype "passive"))
      (node (ref "C328") (pin "1") (pinfunction "1_1") (pintype "passive"))
      (node (ref "C329") (pin "1") (pinfunction "1_1") (pintype "passive"))
      (node (ref "Q300") (pin "6") (pinfunction "6_6") (pintype "passive"))
      (node (ref "Q300") (pin "7") (pinfunction "7_7") (pintype "passive"))
      (node (ref "R305") (pin "2") (pinfunction "2_2") (pintype "passive"))
      (node (ref "R307") (pin "1") (pinfunction "1_1") (pintype "passive"))
      (node (ref "R308") (pin "2") (pinfunction "2_2") (pintype "passive"))
      (node (ref "SW300") (pin "2") (pinfunction "2_2") (pintype "passive"))
      (node (ref "SW301") (pin "2") (pinfunction "2_2") (pintype "passive"))
      (node (ref "SW302") (pin "2") (pinfunction "2_2") (pintype "passive"))
      (node (ref "U300") (pin "105") (pinfunction "VDDLDO_105") (pintype "power_in"))
      (node (ref "U300") (pin "106") (pinfunction "VDD_106") (pintype "power_in"))
      (node (ref "U300") (pin "119") (pinfunction "VDD_119") (pintype "power_in"))
      (node (ref "U300") (pin "129") (pinfunction "VDD_129") (pintype "power_in"))
      (node (ref "U300") (pin "13") (pinfunction "VDD_13") (pintype "power_in"))
      (node (ref "U300") (pin "143") (pinfunction "VDDLDO_143") (pintype "power_in"))
      (node (ref "U300") (pin "144") (pinfunction "VDD_144") (pintype "power_in"))
      (node (ref "U300") (pin "19") (pinfunction "VDD_19") (pintype "power_in"))
      (node (ref "U300") (pin "32") (pinfunction "VDD_32") (pintype "power_in"))
      (node (ref "U300") (pin "35") (pinfunction "VREF+_35") (pintype "power_in"))
      (node (ref "U300") (pin "36") (pinfunction "VDDA_36") (pintype "power_in"))
      (node (ref "U300") (pin "42") (pinfunction "VDD_42") (pintype "power_in"))
      (node (ref "U300") (pin "56") (pinfunction "VDD_56") (pintype "power_in"))
      (node (ref "U300") (pin "7") (pinfunction "VDD_7") (pintype "power_in"))
      (node (ref "U300") (pin "70") (pinfunction "VDDLDO_70") (pintype "power_in"))
      (node (ref "U300") (pin "71") (pinfunction "VDD_71") (pintype "power_in"))
      (node (ref "U300") (pin "79") (pinfunction "VDD_79") (pintype "power_in"))
      (node (ref "U300") (pin "8") (pinfunction "VBAT_8") (pintype "power_in"))
      (node (ref "U300") (pin "92") (pinfunction "VDD_92") (pintype "power_in"))
      (node (ref "U301") (pin "9") (pinfunction "VDD_9") (pintype "power_in"))
      (node (ref "U302") (pin "8") (pinfunction "VCC_8") (pintype "power_in"))
    )
    (net (code "81") (name "GND") (class "Default")
      (node (ref "C300") (pin "2") (pinfunction "2_2") (pintype "passive"))
      (node (ref "C301") (pin "2") (pinfunction "2_2") (pintype "passive"))
      (node (ref "C302") (pin "2") (pinfunction "2_2") (pintype "passive"))
      (node (ref "C303") (pin "2") (pinfunction "2_2") (pintype "passive"))
      (node (ref "C304") (pin "2") (pinfunction "2_2") (pintype "passive"))
      (node (ref "C305") (pin "2") (pinfunction "2_2") (pintype "passive"))
      (node (ref "C306") (pin "2") (pinfunction "2_2") (pintype "passive"))
      (node (ref "C307") (pin "2") (pinfunction "2_2") (pintype "passive"))
      (node (ref "C308") (pin "2") (pinfunction "2_2") (pintype "passive"))
      (node (ref "C309") (pin "2") (pinfunction "2_2") (pintype "passive"))
      (node (ref "C310") (pin "2") (pinfunction "2_2") (pintype "passive"))
      (node (ref "C311") (pin "2") (pinfunction "2_2") (pintype "passive"))
      (node (ref "C312") (pin "2") (pinfunction "2_2") (pintype "passive"))
      (node (ref "C313") (pin "2") (pinfunction "2_2") (pintype "passive"))
      (node (ref "C314") (pin "2") (pinfunction "2_2") (pintype "passive"))
      (node (ref "C315") (pin "2") (pinfunction "2_2") (pintype "passive"))
      (node (ref "C316") (pin "2") (pinfunction "2_2") (pintype "passive"))
      (node (ref "C317") (pin "2") (pinfunction "2_2") (pintype "passive"))
      (node (ref "C318") (pin "2") (pinfunction "2_2") (pintype "passive"))
      (node (ref "C319") (pin "2") (pinfunction "2_2") (pintype "passive"))
      (node (ref "C320") (pin "2") (pinfunction "2_2") (pintype "passive"))
      (node (ref "C321") (pin "2") (pinfunction "2_2") (pintype "passive"))
      (node (ref "C322") (pin "2") (pinfunction "2_2") (pintype "passive"))
      (node (ref "C323") (pin "2") (pinfunction "2_2") (pintype "passive"))
      (node (ref "C324") (pin "2") (pinfunction "2_2") (pintype "passive"))
      (node (ref "C325") (pin "2") (pinfunction "2_2") (pintype "passive"))
      (node (ref "C326") (pin "2") (pinfunction "2_2") (pintype "passive"))
      (node (ref "C327") (pin "2") (pinfunction "2_2") (pintype "passive"))
      (node (ref "C328") (pin "2") (pinfunction "2_2") (pintype "passive"))
      (node (ref "C329") (pin "2") (pinfunction "2_2") (pintype "passive"))
      (node (ref "LS300") (pin "1") (pinfunction "NEG_1") (pintype "passive"))
      (node (ref "Q300") (pin "3") (pinfunction "3_3") (pintype "passive"))
      (node (ref "Q300") (pin "4") (pinfunction "4_4") (pintype "passive"))
      (node (ref "Q300") (pin "5") (pinfunction "5_5") (pintype "passive"))
      (node (ref "Q300") (pin "8") (pinfunction "8_8") (pintype "passive"))
      (node (ref "R301") (pin "2") (pinfunction "2_2") (pintype "passive"))
      (node (ref "R302") (pin "1") (pinfunction "1_1") (pintype "passive"))
      (node (ref "R303") (pin "1") (pinfunction "1_1") (pintype "passive"))
      (node (ref "R304") (pin "1") (pinfunction "1_1") (pintype "passive"))
      (node (ref "R309") (pin "2") (pinfunction "2_2") (pintype "passive"))
      (node (ref "U300") (pin "104") (pinfunction "VSS_104") (pintype "power_in"))
      (node (ref "U300") (pin "118") (pinfunction "VSS_118") (pintype "power_in"))
      (node (ref "U300") (pin "12") (pinfunction "VSS_12") (pintype "power_in"))
      (node (ref "U300") (pin "128") (pinfunction "VSS_128") (pintype "power_in"))
      (node (ref "U300") (pin "141") (pinfunction "VSS_141") (pintype "power_in"))
      (node (ref "U300") (pin "18") (pinfunction "VSS_18") (pintype "power_in"))
      (node (ref "U300") (pin "33") (pinfunction "VSS_33") (pintype "power_in"))
      (node (ref "U300") (pin "34") (pinfunction "VSSA_34") (pintype "power_in"))
      (node (ref "U300") (pin "41") (pinfunction "VSS_41") (pintype "power_in"))
      (node (ref "U300") (pin "55") (pinfunction "VSS_55") (pintype "power_in"))
      (node (ref "U300") (pin "6") (pinfunction "VSS_6") (pintype "power_in"))
      (node (ref "U300") (pin "69") (pinfunction "VSS_69") (pintype "power_in"))
      (node (ref "U300") (pin "80") (pinfunction "VSS_80") (pintype "power_in"))
      (node (ref "U300") (pin "89") (pinfunction "VSS_89") (pintype "power_in"))
      (node (ref "U301") (pin "7") (pinfunction "VSS_7") (pintype "power_in"))
      (node (ref "U302") (pin "4") (pinfunction "GND_4") (pintype "power_in"))
      (node (ref "Y300") (pin "2") (pinfunction "GND_2") (pintype "passive"))
      (node (ref "Y300") (pin "4") (pinfunction "GND_4") (pintype "passive"))
    )
    (net (code "82") (name "Net-(C300-Pad1)") (class "Default")
      (node (ref "C300") (pin "1") (pinfunction "1_1") (pintype "passive"))
      (node (ref "R306") (pin "2") (pinfunction "2_2") (pintype "passive"))
      (node (ref "Y300") (pin "1") (pinfunction "Crystal_1") (pintype "passive"))
    )
    (net (code "83") (name "Net-(LS300-POS)") (class "Default")
      (node (ref "LS300") (pin "2") (pinfunction "POS_2") (pintype "passive"))
      (node (ref "Q300") (pin "1") (pinfunction "1_1") (pintype "passive"))
      (node (ref "R309") (pin "1") (pinfunction "1_1") (pintype "passive"))
    )
    (net (code "84") (name "Net-(Q300-Pad2)") (class "Default")
      (node (ref "Q300") (pin "2") (pinfunction "2_2") (pintype "passive"))
      (node (ref "R300") (pin "2") (pinfunction "2_2") (pintype "passive"))
      (node (ref "R301") (pin "1") (pinfunction "1_1") (pintype "passive"))
    )
    (net (code "85") (name "Net-(U300C-VDD33USB)") (class "Default")
      (node (ref "C321") (pin "1") (pinfunction "1_1") (pintype "passive"))
      (node (ref "U300") (pin "91") (pinfunction "VDD33USB_91") (pintype "power_in"))
    )
    (net (code "86") (name "Net-(U301-VCAP)") (class "Default")
      (node (ref "C327") (pin "1") (pinfunction "1_1") (pintype "passive"))
      (node (ref "U301") (pin "8") (pinfunction "VCAP_8") (pintype "power_in"))
    )
    (net (code "87") (name "unconnected-(U300A-PA15-Pad108)") (class "Default")
      (node (ref "U300") (pin "108") (pinfunction "PA15_108") (pintype "bidirectional"))
    )
    (net (code "88") (name "unconnected-(U300A-PB2-Pad51)") (class "Default")
      (node (ref "U300") (pin "51") (pinfunction "PB2_51") (pintype "bidirectional"))
    )
    (net (code "89") (name "unconnected-(U300A-PB12-Pad72)") (class "Default")
      (node (ref "U300") (pin "72") (pinfunction "PB12_72") (pintype "bidirectional"))
    )
    (net (code "90") (name "unconnected-(U300A-PC5-Pad48)") (class "Default")
      (node (ref "U300") (pin "48") (pinfunction "PC5_48") (pintype "bidirectional"))
    )
    (net (code "91") (name "unconnected-(U300A-PC14-OSC32_IN-Pad10)") (class "Default")
      (node (ref "U300") (pin "10") (pinfunction "PC14-OSC32_IN_10") (pintype "bidirectional+no_connect"))
    )
    (net (code "92") (name "unconnected-(U300A-PD2-Pad114)") (class "Default")
      (node (ref "U300") (pin "114") (pinfunction "PD2_114") (pintype "bidirectional"))
    )
    (net (code "93") (name "unconnected-(U300A-PD3-Pad115)") (class "Default")
      (node (ref "U300") (pin "115") (pinfunction "PD3_115") (pintype "bidirectional"))
    )
    (net (code "94") (name "unconnected-(U300A-PD4-Pad116)") (class "Default")
      (node (ref "U300") (pin "116") (pinfunction "PD4_116") (pintype "bidirectional"))
    )
    (net (code "95") (name "unconnected-(U300A-PD5-Pad117)") (class "Default")
      (node (ref "U300") (pin "117") (pinfunction "PD5_117") (pintype "bidirectional"))
    )
    (net (code "96") (name "unconnected-(U300A-PD6-Pad120)") (class "Default")
      (node (ref "U300") (pin "120") (pinfunction "PD6_120") (pintype "bidirectional"))
    )
    (net (code "97") (name "unconnected-(U300A-PD7-Pad121)") (class "Default")
      (node (ref "U300") (pin "121") (pinfunction "PD7_121") (pintype "bidirectional"))
    )
    (net (code "98") (name "unconnected-(U300A-PD8-Pad76)") (class "Default")
      (node (ref "U300") (pin "76") (pinfunction "PD8_76") (pintype "bidirectional"))
    )
    (net (code "99") (name "unconnected-(U300A-PD9-Pad77)") (class "Default")
      (node (ref "U300") (pin "77") (pinfunction "PD9_77") (pintype "bidirectional"))
    )
    (net (code "100") (name "unconnected-(U300A-PD10-Pad78)") (class "Default")
      (node (ref "U300") (pin "78") (pinfunction "PD10_78") (pintype "bidirectional"))
    )
    (net (code "101") (name "unconnected-(U300A-PD11-Pad81)") (class "Default")
      (node (ref "U300") (pin "81") (pinfunction "PD11_81") (pintype "bidirectional"))
    )
    (net (code "102") (name "unconnected-(U300A-PD13-Pad83)") (class "Default")
      (node (ref "U300") (pin "83") (pinfunction "PD13_83") (pintype "bidirectional"))
    )
    (net (code "103") (name "unconnected-(U300A-PD15-Pad85)") (class "Default")
      (node (ref "U300") (pin "85") (pinfunction "PD15_85") (pintype "bidirectional"))
    )
    (net (code "104") (name "unconnected-(U300B-PDR_ON-Pad142)") (class "Default")
      (node (ref "U300") (pin "142") (pinfunction "PDR_ON_142") (pintype "bidirectional"))
    )
    (net (code "105") (name "unconnected-(U300B-PG6-Pad86)") (class "Default")
      (node (ref "U300") (pin "86") (pinfunction "PG6_86") (pintype "bidirectional"))
    )
    (net (code "106") (name "unconnected-(U300B-PG7-Pad87)") (class "Default")
      (node (ref "U300") (pin "87") (pinfunction "PG7_87") (pintype "bidirectional"))
    )
    (net (code "107") (name "unconnected-(U300B-PG8-Pad88)") (class "Default")
      (node (ref "U300") (pin "88") (pinfunction "PG8_88") (pintype "bidirectional"))
    )
    (net (code "108") (name "unconnected-(U300B-PG9-Pad122)") (class "Default")
      (node (ref "U300") (pin "122") (pinfunction "PG9_122") (pintype "bidirectional"))
    )
    (net (code "109") (name "unconnected-(U300B-PG10-Pad123)") (class "Default")
      (node (ref "U300") (pin "123") (pinfunction "PG10_123") (pintype "bidirectional"))
    )
    (net (code "110") (name "unconnected-(U300B-PG11-Pad124)") (class "Default")
      (node (ref "U300") (pin "124") (pinfunction "PG11_124") (pintype "bidirectional"))
    )
    (net (code "111") (name "unconnected-(U300B-PG12-Pad125)") (class "Default")
      (node (ref "U300") (pin "125") (pinfunction "PG12_125") (pintype "bidirectional"))
    )
    (net (code "112") (name "unconnected-(U300B-PG13-Pad126)") (class "Default")
      (node (ref "U300") (pin "126") (pinfunction "PG13_126") (pintype "bidirectional"))
    )
    (net (code "113") (name "unconnected-(U300B-PG14-Pad127)") (class "Default")
      (node (ref "U300") (pin "127") (pinfunction "PG14_127") (pintype "bidirectional"))
    )
    (net (code "114") (name "unconnected-(U300C-VDDSMPS-Pad16)") (class "Default")
      (node (ref "U300") (pin "16") (pinfunction "VDDSMPS_16") (pintype "power_in+no_connect"))
    )
    (net (code "115") (name "unconnected-(U300C-VFBSMPS-Pad17)") (class "Default")
      (node (ref "U300") (pin "17") (pinfunction "VFBSMPS_17") (pintype "power_in+no_connect"))
    )
    (net (code "116") (name "unconnected-(U300C-VLXSMPS-Pad15)") (class "Default")
      (node (ref "U300") (pin "15") (pinfunction "VLXSMPS_15") (pintype "power_in+no_connect"))
    )
    (net (code "117") (name "unconnected-(U300C-VSSSMPS-Pad14)") (class "Default")
      (node (ref "U300") (pin "14") (pinfunction "VSSSMPS_14") (pintype "power_in+no_connect"))
    )
    (net (code "118") (name "unconnected-(U301-NRST-Pad4)") (class "Default")
      (node (ref "U301") (pin "4") (pinfunction "NRST_4") (pintype "bidirectional"))
    )
    (net (code "119") (name "unconnected-(U301-PA1{slash}OSCIN-Pad5)") (class "Default")
      (node (ref "U301") (pin "5") (pinfunction "PA1/OSCIN_5") (pintype "bidirectional"))
    )
    (net (code "120") (name "unconnected-(U301-PA2{slash}OSCOUT-Pad6)") (class "Default")
      (node (ref "U301") (pin "6") (pinfunction "PA2/OSCOUT_6") (pintype "bidirectional"))
    )
    (net (code "121") (name "unconnected-(U301-PA3(HS){slash}TIM2_CH3(SPI_NSS)-Pad10)") (class "Default")
      (node (ref "U301") (pin "10") (pinfunction "PA3(HS)/TIM2_CH3(SPI_NSS)_10") (pintype "bidirectional"))
    )
    (net (code "122") (name "unconnected-(U301-PD3(HS){slash}AIN4{slash}TIM2_CH2{slash}ADC_ETR-Pad20)") (class "Default")
      (node (ref "U301") (pin "20") (pinfunction "PD3(HS)/AIN4/TIM2_CH2/ADC_ETR_20") (pintype "bidirectional"))
    )
    (net (code "123") (name "unconnected-(U301-PD4(HS){slash}BEEP{slash}TIM2_CH1{slash}UART1_CK-Pad1)") (class "Default")
      (node (ref "U301") (pin "1") (pinfunction "PD4(HS)/BEEP/TIM2_CH1/UART1_CK_1") (pintype "bidirectional"))
    )
    (net (code "124") (name "unconnected-(U301-PD5(HS){slash}AIN5{slash}UART1_TX-Pad2)") (class "Default")
      (node (ref "U301") (pin "2") (pinfunction "PD5(HS)/AIN5/UART1_TX_2") (pintype "bidirectional"))
    )
    (net (code "125") (name "unconnected-(U301-PD6(HS){slash}AIN6{slash}UART1_RX-Pad3)") (class "Default")
      (node (ref "U301") (pin "3") (pinfunction "PD6(HS)/AIN6/UART1_RX_3") (pintype "bidirectional"))
    )
  )
)
